# Sheet1.net
KiCad netlist of a schematic drawn in Altium Designer
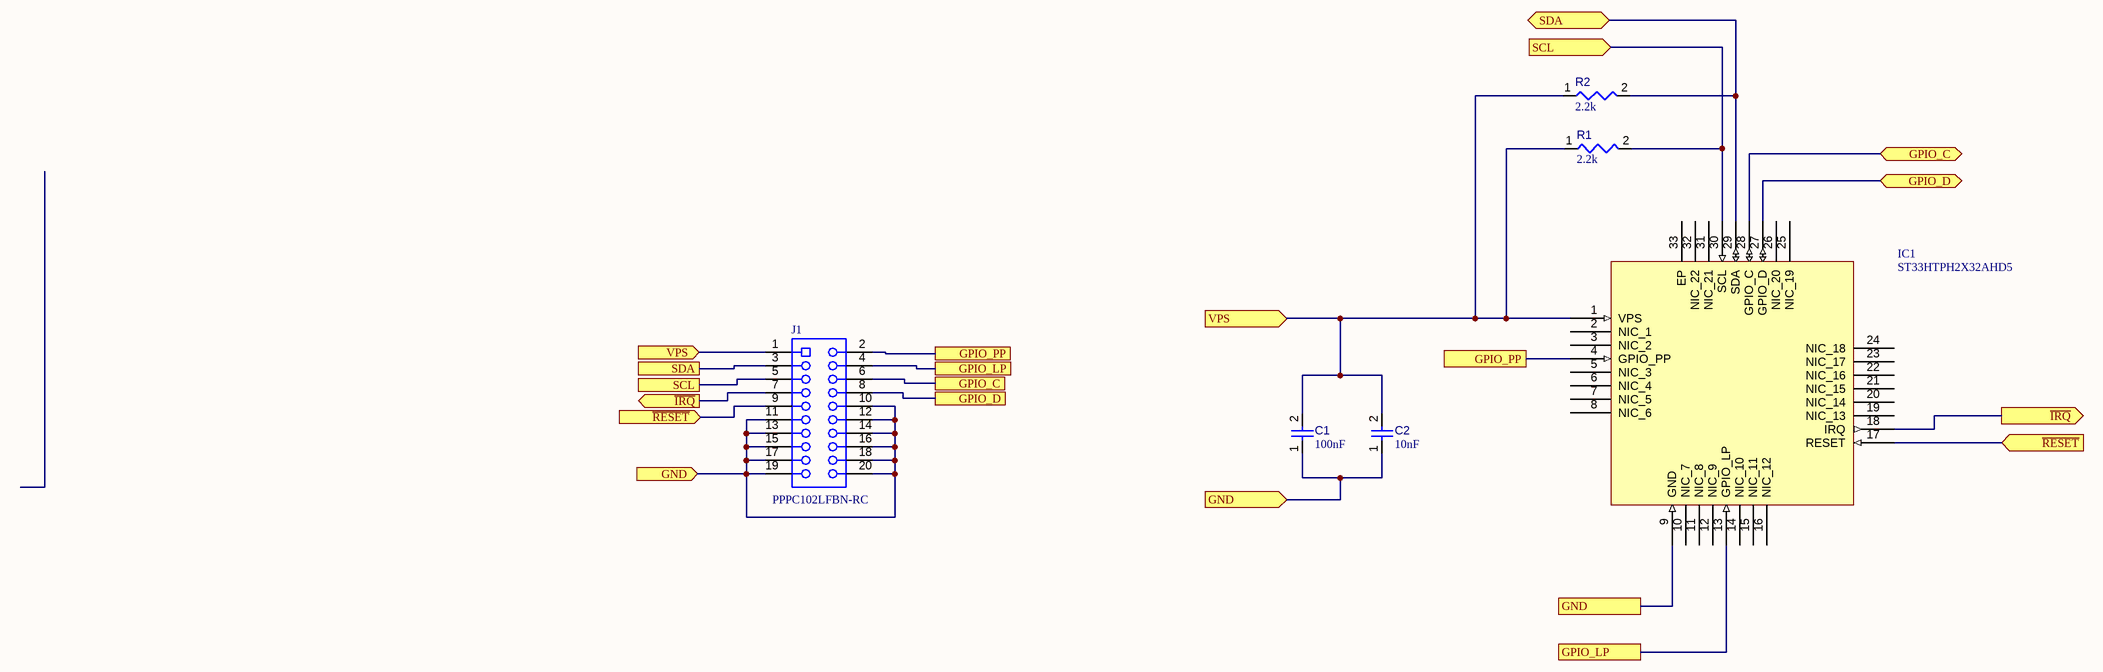
[diagram p0: Sheet1.SchDoc]

(export (version "E")
  (design (tool "Eeschema 10.0.6"))
  (components
    (comp (ref "C1")
      (value "100nF")
      (footprint "CAPC0402(1005)60_L")
      (description "Chip Capacitor, 100nF +/-20%, 10V, 0402, Thickness 0.6 mm")
      (fields (field (name "TOLERANCE") "20%") (field (name "Comment") "Capacitor 100nF +/-20% 10V 0402"))
      (libsource (lib "Personal Workspace") (part "CAP-NP-2"))
    )
    (comp (ref "C2")
      (value "10nF")
      (footprint "CAPC0402(1005)60_L")
      (description "Chip Capacitor, 10nF +/-20%, 50V, 0402, Thickness 0.6 mm")
      (fields (field (name "TOLERANCE") "5%") (field (name "Comment") "Capacitor 10nF +/-20% 50V 0402"))
      (libsource (lib "Personal Workspace") (part "CAP-NP-2"))
    )
    (comp (ref "IC1")
      (value "ST33HTPH2X32AHD5")
      (footprint "QFN50P500X500X100-33N-D")
      (description "Microprocessor Circuit - Long-term evolution TPM 2.0 device with an I2C interface")
      (libsource (lib "Personal Workspace") (part "New symbol 1"))
    )
    (comp (ref "J1")
      (value "PPPC102LFBN-RC")
      (footprint "SLIN-PPPC102LFBN-RC_V")
      (fields (field (name "MANUFACTURER") "Sullins"))
      (libsource (lib "Personal Workspace") (part "CN-2P-F-R20"))
    )
    (comp (ref "R1")
      (value "2.2k")
      (footprint "RESC0402(1005)_L")
      (description "Chip Resistor, 2,2 kOhms, +/-5 %, 63 mW, -55 to 155 degC, 0402")
      (fields (field (name "POWER") "63mW") (field (name "TOLERANCE") "5%"))
      (libsource (lib "Personal Workspace") (part "RES-2"))
    )
    (comp (ref "R2")
      (value "2.2k")
      (footprint "RESC0402(1005)_L")
      (description "Chip Resistor, 2,2 kOhms, +/-5 %, 63 mW, -55 to 155 degC, 0402")
      (fields (field (name "POWER") "63mW") (field (name "TOLERANCE") "5%"))
      (libsource (lib "Personal Workspace") (part "RES-2"))
    )
  )
  (nets
    (net (code "1") (name "/GND") (class "Default")
      (node (ref "C1") (pin "1") (pinfunction "1_1") (pintype "passive"))
      (node (ref "C2") (pin "1") (pinfunction "1_1") (pintype "passive"))
      (node (ref "IC1") (pin "9") (pinfunction "GND_9") (pintype "input"))
      (node (ref "J1") (pin "10") (pinfunction "10_10") (pintype "passive"))
      (node (ref "J1") (pin "11") (pinfunction "11_11") (pintype "passive"))
      (node (ref "J1") (pin "12") (pinfunction "12_12") (pintype "passive"))
      (node (ref "J1") (pin "13") (pinfunction "13_13") (pintype "passive"))
      (node (ref "J1") (pin "14") (pinfunction "14_14") (pintype "passive"))
      (node (ref "J1") (pin "15") (pinfunction "15_15") (pintype "passive"))
      (node (ref "J1") (pin "16") (pinfunction "16_16") (pintype "passive"))
      (node (ref "J1") (pin "17") (pinfunction "17_17") (pintype "passive"))
      (node (ref "J1") (pin "18") (pinfunction "18_18") (pintype "passive"))
      (node (ref "J1") (pin "19") (pinfunction "19_19") (pintype "passive"))
      (node (ref "J1") (pin "20") (pinfunction "20_20") (pintype "passive"))
    )
    (net (code "2") (name "/GPIO_C") (class "Default")
      (node (ref "IC1") (pin "28") (pinfunction "GPIO_C_28") (pintype "bidirectional"))
      (node (ref "J1") (pin "6") (pinfunction "6_6") (pintype "passive"))
    )
    (net (code "3") (name "/GPIO_D") (class "Default")
      (node (ref "IC1") (pin "27") (pinfunction "GPIO_D_27") (pintype "bidirectional"))
      (node (ref "J1") (pin "8") (pinfunction "8_8") (pintype "passive"))
    )
    (net (code "4") (name "/GPIO_LP") (class "Default")
      (node (ref "IC1") (pin "13") (pinfunction "GPIO_LP_13") (pintype "input"))
      (node (ref "J1") (pin "4") (pinfunction "4_4") (pintype "passive"))
    )
    (net (code "5") (name "/GPIO_PP") (class "Default")
      (node (ref "IC1") (pin "4") (pinfunction "GPIO_PP_4") (pintype "input"))
      (node (ref "J1") (pin "2") (pinfunction "2_2") (pintype "passive"))
    )
    (net (code "6") (name "/SCL") (class "Default")
      (node (ref "IC1") (pin "30") (pinfunction "SCL_30") (pintype "input"))
      (node (ref "J1") (pin "5") (pinfunction "5_5") (pintype "passive"))
      (node (ref "R1") (pin "2") (pinfunction "2_2") (pintype "passive"))
    )
    (net (code "7") (name "/SDA") (class "Default")
      (node (ref "IC1") (pin "29") (pinfunction "SDA_29") (pintype "bidirectional"))
      (node (ref "J1") (pin "3") (pinfunction "3_3") (pintype "passive"))
      (node (ref "R2") (pin "2") (pinfunction "2_2") (pintype "passive"))
    )
    (net (code "8") (name "/VPS") (class "Default")
      (node (ref "C1") (pin "2") (pinfunction "2_2") (pintype "passive"))
      (node (ref "C2") (pin "2") (pinfunction "2_2") (pintype "passive"))
      (node (ref "IC1") (pin "1") (pinfunction "VPS_1") (pintype "input"))
      (node (ref "J1") (pin "1") (pinfunction "1_1") (pintype "passive"))
      (node (ref "R1") (pin "1") (pinfunction "1_1") (pintype "passive"))
      (node (ref "R2") (pin "1") (pinfunction "1_1") (pintype "passive"))
    )
    (net (code "9") (name "/~{IRQ}") (class "Default")
      (node (ref "IC1") (pin "18") (pinfunction "IRQ_18") (pintype "output"))
      (node (ref "J1") (pin "7") (pinfunction "7_7") (pintype "passive"))
    )
    (net (code "10") (name "/~{RESET}") (class "Default")
      (node (ref "IC1") (pin "17") (pinfunction "RESET_17") (pintype "input"))
      (node (ref "J1") (pin "9") (pinfunction "9_9") (pintype "passive"))
    )
    (net (code "11") (name "unconnected-(IC1-EP-Pad33)") (class "Default")
      (node (ref "IC1") (pin "33") (pinfunction "EP_33") (pintype "tri_state"))
    )
    (net (code "12") (name "unconnected-(IC1-NIC_1-Pad2)") (class "Default")
      (node (ref "IC1") (pin "2") (pinfunction "NIC_1_2") (pintype "tri_state"))
    )
    (net (code "13") (name "unconnected-(IC1-NIC_2-Pad3)") (class "Default")
      (node (ref "IC1") (pin "3") (pinfunction "NIC_2_3") (pintype "tri_state"))
    )
    (net (code "14") (name "unconnected-(IC1-NIC_3-Pad5)") (class "Default")
      (node (ref "IC1") (pin "5") (pinfunction "NIC_3_5") (pintype "tri_state"))
    )
    (net (code "15") (name "unconnected-(IC1-NIC_4-Pad6)") (class "Default")
      (node (ref "IC1") (pin "6") (pinfunction "NIC_4_6") (pintype "tri_state"))
    )
    (net (code "16") (name "unconnected-(IC1-NIC_5-Pad7)") (class "Default")
      (node (ref "IC1") (pin "7") (pinfunction "NIC_5_7") (pintype "tri_state"))
    )
    (net (code "17") (name "unconnected-(IC1-NIC_6-Pad8)") (class "Default")
      (node (ref "IC1") (pin "8") (pinfunction "NIC_6_8") (pintype "tri_state"))
    )
    (net (code "18") (name "unconnected-(IC1-NIC_7-Pad10)") (class "Default")
      (node (ref "IC1") (pin "10") (pinfunction "NIC_7_10") (pintype "tri_state"))
    )
    (net (code "19") (name "unconnected-(IC1-NIC_8-Pad11)") (class "Default")
      (node (ref "IC1") (pin "11") (pinfunction "NIC_8_11") (pintype "tri_state"))
    )
    (net (code "20") (name "unconnected-(IC1-NIC_9-Pad12)") (class "Default")
      (node (ref "IC1") (pin "12") (pinfunction "NIC_9_12") (pintype "tri_state"))
    )
    (net (code "21") (name "unconnected-(IC1-NIC_10-Pad14)") (class "Default")
      (node (ref "IC1") (pin "14") (pinfunction "NIC_10_14") (pintype "tri_state"))
    )
    (net (code "22") (name "unconnected-(IC1-NIC_11-Pad15)") (class "Default")
      (node (ref "IC1") (pin "15") (pinfunction "NIC_11_15") (pintype "tri_state"))
    )
    (net (code "23") (name "unconnected-(IC1-NIC_12-Pad16)") (class "Default")
      (node (ref "IC1") (pin "16") (pinfunction "NIC_12_16") (pintype "tri_state"))
    )
    (net (code "24") (name "unconnected-(IC1-NIC_13-Pad19)") (class "Default")
      (node (ref "IC1") (pin "19") (pinfunction "NIC_13_19") (pintype "tri_state"))
    )
    (net (code "25") (name "unconnected-(IC1-NIC_14-Pad20)") (class "Default")
      (node (ref "IC1") (pin "20") (pinfunction "NIC_14_20") (pintype "tri_state"))
    )
    (net (code "26") (name "unconnected-(IC1-NIC_15-Pad21)") (class "Default")
      (node (ref "IC1") (pin "21") (pinfunction "NIC_15_21") (pintype "tri_state"))
    )
    (net (code "27") (name "unconnected-(IC1-NIC_16-Pad22)") (class "Default")
      (node (ref "IC1") (pin "22") (pinfunction "NIC_16_22") (pintype "tri_state"))
    )
    (net (code "28") (name "unconnected-(IC1-NIC_17-Pad23)") (class "Default")
      (node (ref "IC1") (pin "23") (pinfunction "NIC_17_23") (pintype "tri_state"))
    )
    (net (code "29") (name "unconnected-(IC1-NIC_18-Pad24)") (class "Default")
      (node (ref "IC1") (pin "24") (pinfunction "NIC_18_24") (pintype "tri_state"))
    )
    (net (code "30") (name "unconnected-(IC1-NIC_19-Pad25)") (class "Default")
      (node (ref "IC1") (pin "25") (pinfunction "NIC_19_25") (pintype "tri_state"))
    )
    (net (code "31") (name "unconnected-(IC1-NIC_20-Pad26)") (class "Default")
      (node (ref "IC1") (pin "26") (pinfunction "NIC_20_26") (pintype "tri_state"))
    )
    (net (code "32") (name "unconnected-(IC1-NIC_21-Pad31)") (class "Default")
      (node (ref "IC1") (pin "31") (pinfunction "NIC_21_31") (pintype "tri_state"))
    )
    (net (code "33") (name "unconnected-(IC1-NIC_22-Pad32)") (class "Default")
      (node (ref "IC1") (pin "32") (pinfunction "NIC_22_32") (pintype "tri_state"))
    )
  )
)
